# LINMOD.net
KiCad netlist of a schematic drawn in EAGLE
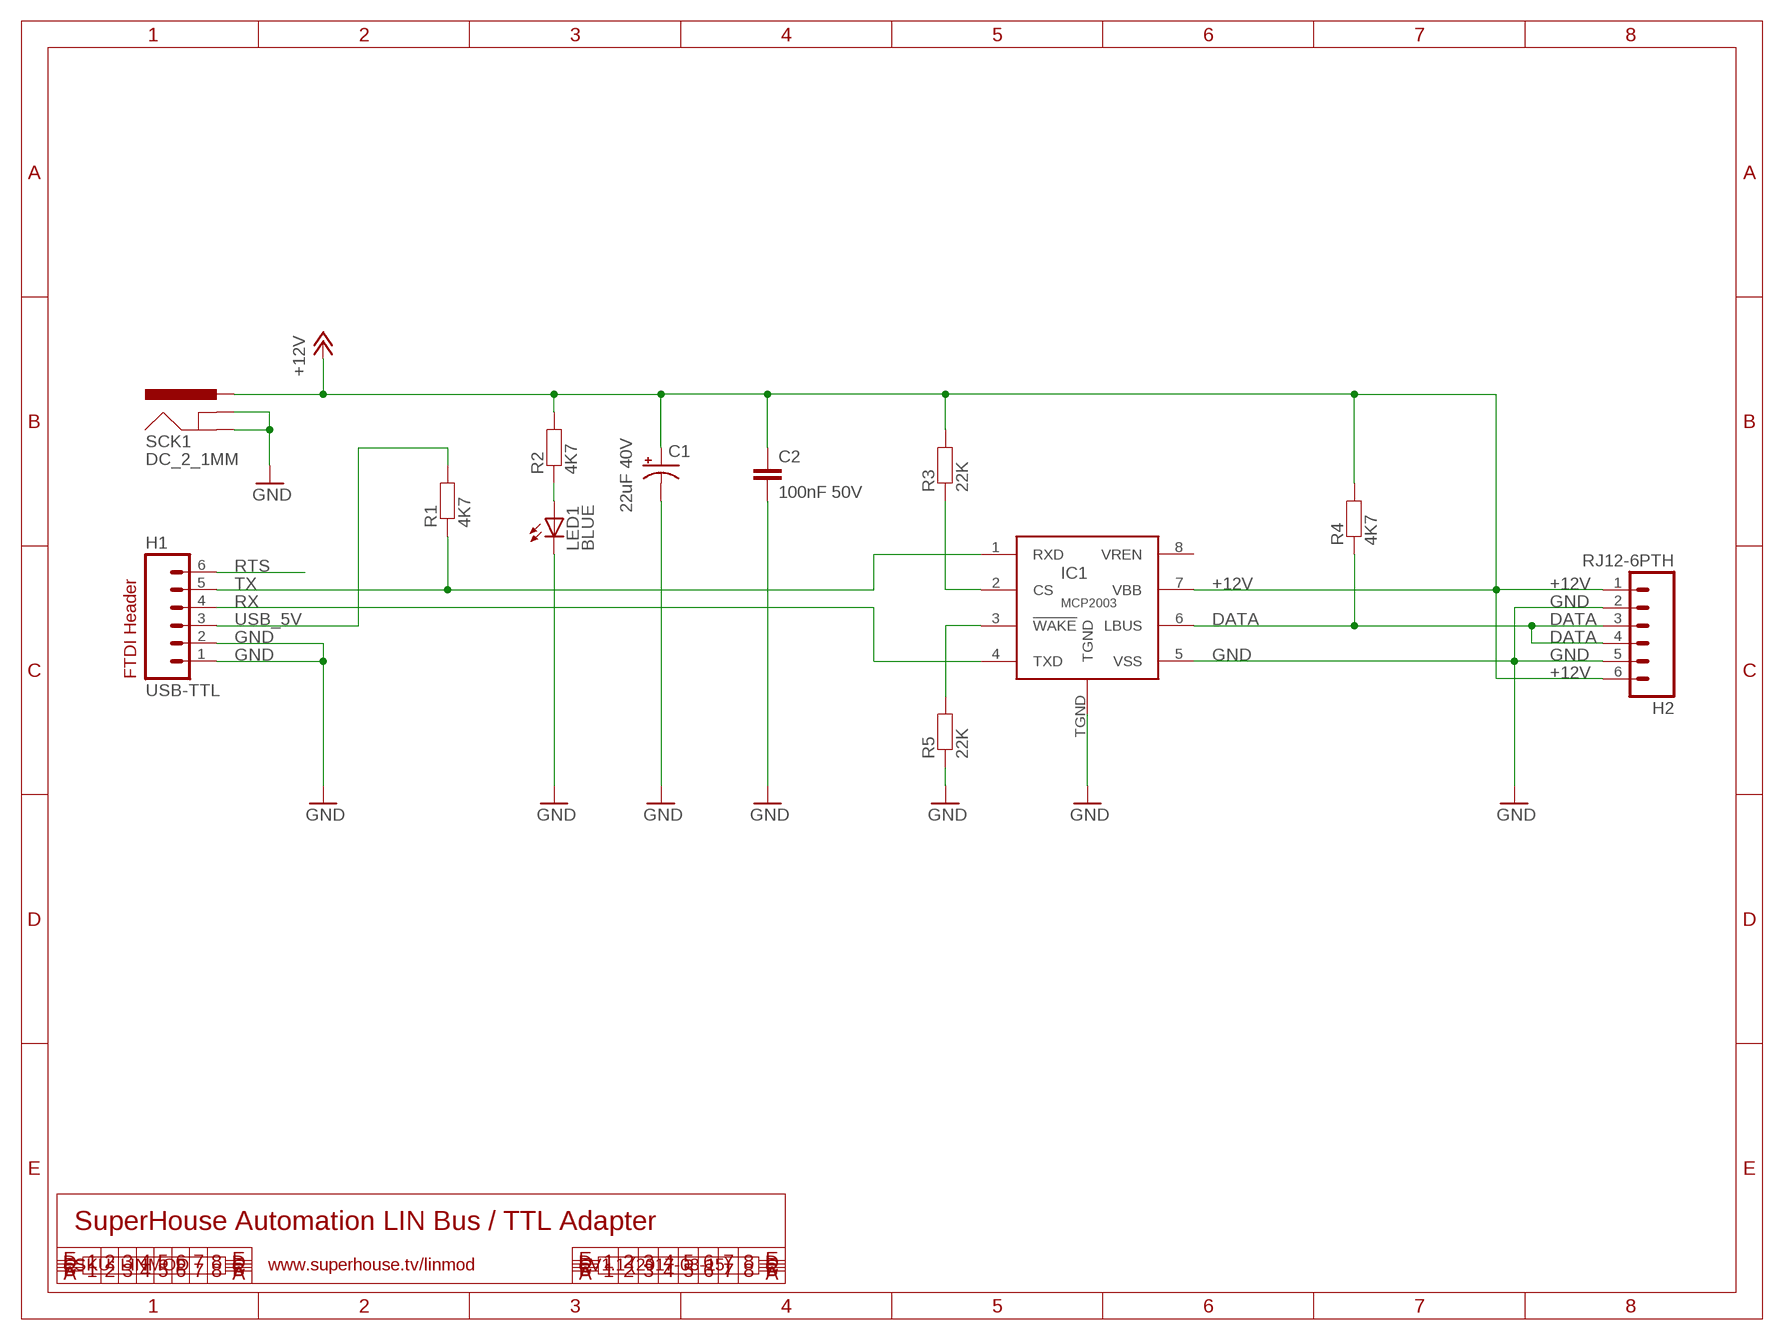
[diagram p0: schematic, sheet 1]

(export (version "E")
  (design (tool "Eeschema 10.0.6"))
  (components
    (comp (ref "C1")
      (value "22uF 40V")
      (footprint "eagle-import:UD-6,3X5,8_NICHICON")
      (libsource (lib "eagle-import") (part "CPOL-USUD-6,3X5,8"))
    )
    (comp (ref "C2")
      (value "100nF 50V")
      (footprint "eagle-import:0603")
      (libsource (lib "eagle-import") (part "CAP0603"))
    )
    (comp (ref "H1")
      (value "USB-TTL")
      (footprint "eagle-import:1X06")
      (libsource (lib "eagle-import") (part "M06SIP"))
    )
    (comp (ref "H2")
      (value "RJ12-6PTH")
      (footprint "eagle-import:RJ12-6")
      (libsource (lib "eagle-import") (part "RJ12-6PTH"))
    )
    (comp (ref "IC1")
      (value "MCP2003")
      (footprint "eagle-import:SOIC8T")
      (libsource (lib "eagle-import") (part "MCP2003"))
    )
    (comp (ref "LED1")
      (value "BLUE")
      (footprint "eagle-import:LED-0603")
      (libsource (lib "eagle-import") (part "LED0603"))
    )
    (comp (ref "R1")
      (value "4K7")
      (footprint "eagle-import:0603")
      (libsource (lib "eagle-import") (part "RESISTOR0603"))
    )
    (comp (ref "R2")
      (value "4K7")
      (footprint "eagle-import:0603")
      (libsource (lib "eagle-import") (part "RESISTOR0603"))
    )
    (comp (ref "R3")
      (value "22K")
      (footprint "eagle-import:0603")
      (libsource (lib "eagle-import") (part "RESISTOR0603"))
    )
    (comp (ref "R4")
      (value "4K7")
      (footprint "eagle-import:0603")
      (libsource (lib "eagle-import") (part "RESISTOR0603"))
    )
    (comp (ref "R5")
      (value "22K")
      (footprint "eagle-import:0603")
      (libsource (lib "eagle-import") (part "RESISTOR0603"))
    )
    (comp (ref "SCK1")
      (value "DC_2_1MM")
      (footprint "eagle-import:POWER_JACK_PTH")
      (libsource (lib "eagle-import") (part "POWER_JACKPTH"))
    )
  )
  (nets
    (net (code "1") (name "+12V") (class "Default")
      (node (ref "C1") (pin "+") (pinfunction "+_+") (pintype "passive"))
      (node (ref "C2") (pin "1") (pinfunction "1_1") (pintype "passive"))
      (node (ref "H2") (pin "1") (pinfunction "1_1") (pintype "passive"))
      (node (ref "H2") (pin "6") (pinfunction "6_6") (pintype "passive"))
      (node (ref "IC1") (pin "7") (pinfunction "VBB_7") (pintype "power_in"))
      (node (ref "R2") (pin "2") (pinfunction "2_2") (pintype "passive"))
      (node (ref "R3") (pin "2") (pinfunction "2_2") (pintype "passive"))
      (node (ref "R4") (pin "2") (pinfunction "2_2") (pintype "passive"))
      (node (ref "SCK1") (pin "PWR") (pinfunction "PWR_PWR") (pintype "bidirectional"))
    )
    (net (code "2") (name "/DATA") (class "Default")
      (node (ref "H2") (pin "3") (pinfunction "3_3") (pintype "passive"))
      (node (ref "H2") (pin "4") (pinfunction "4_4") (pintype "passive"))
      (node (ref "IC1") (pin "6") (pinfunction "LBUS_6") (pintype "bidirectional"))
      (node (ref "R4") (pin "1") (pinfunction "1_1") (pintype "passive"))
    )
    (net (code "3") (name "/RTS") (class "Default")
      (node (ref "H1") (pin "6") (pinfunction "6_6") (pintype "passive"))
    )
    (net (code "4") (name "/RX") (class "Default")
      (node (ref "H1") (pin "4") (pinfunction "4_4") (pintype "passive"))
      (node (ref "IC1") (pin "4") (pinfunction "TXD_4") (pintype "output"))
    )
    (net (code "5") (name "/TX") (class "Default")
      (node (ref "H1") (pin "5") (pinfunction "5_5") (pintype "passive"))
      (node (ref "IC1") (pin "1") (pinfunction "RXD_1") (pintype "input"))
      (node (ref "R1") (pin "1") (pinfunction "1_1") (pintype "passive"))
    )
    (net (code "6") (name "/USB_5V") (class "Default")
      (node (ref "H1") (pin "3") (pinfunction "3_3") (pintype "passive"))
      (node (ref "R1") (pin "2") (pinfunction "2_2") (pintype "passive"))
    )
    (net (code "7") (name "GND") (class "Default")
      (node (ref "C1") (pin "-") (pinfunction "-_-") (pintype "passive"))
      (node (ref "C2") (pin "2") (pinfunction "2_2") (pintype "passive"))
      (node (ref "H1") (pin "1") (pinfunction "1_1") (pintype "passive"))
      (node (ref "H1") (pin "2") (pinfunction "2_2") (pintype "passive"))
      (node (ref "H2") (pin "2") (pinfunction "2_2") (pintype "passive"))
      (node (ref "H2") (pin "5") (pinfunction "5_5") (pintype "passive"))
      (node (ref "IC1") (pin "5") (pinfunction "VSS_5") (pintype "power_in"))
      (node (ref "IC1") (pin "TGND") (pinfunction "TGND_TGND") (pintype "power_in"))
      (node (ref "LED1") (pin "C") (pinfunction "C_C") (pintype "passive"))
      (node (ref "R5") (pin "1") (pinfunction "1_1") (pintype "passive"))
      (node (ref "SCK1") (pin "GND") (pinfunction "GND_GND") (pintype "bidirectional"))
      (node (ref "SCK1") (pin "GNDBREAK") (pinfunction "GNDBREAK_GNDBREAK") (pintype "bidirectional"))
    )
    (net (code "8") (name "Net-(IC1-CS)") (class "Default")
      (node (ref "IC1") (pin "2") (pinfunction "CS_2") (pintype "input"))
      (node (ref "R3") (pin "1") (pinfunction "1_1") (pintype "passive"))
    )
    (net (code "9") (name "Net-(IC1-~{WAKE})") (class "Default")
      (node (ref "IC1") (pin "3") (pinfunction "~{WAKE}_3") (pintype "input"))
      (node (ref "R5") (pin "2") (pinfunction "2_2") (pintype "passive"))
    )
    (net (code "10") (name "Net-(LED1-PadA)") (class "Default")
      (node (ref "LED1") (pin "A") (pinfunction "A_A") (pintype "passive"))
      (node (ref "R2") (pin "1") (pinfunction "1_1") (pintype "passive"))
    )
    (net (code "11") (name "unconnected-(IC1-VREN-Pad8)") (class "Default")
      (node (ref "IC1") (pin "8") (pinfunction "VREN_8") (pintype "output"))
    )
  )
)
